# Power.net
KiCad netlist of a schematic drawn in Altium Designer
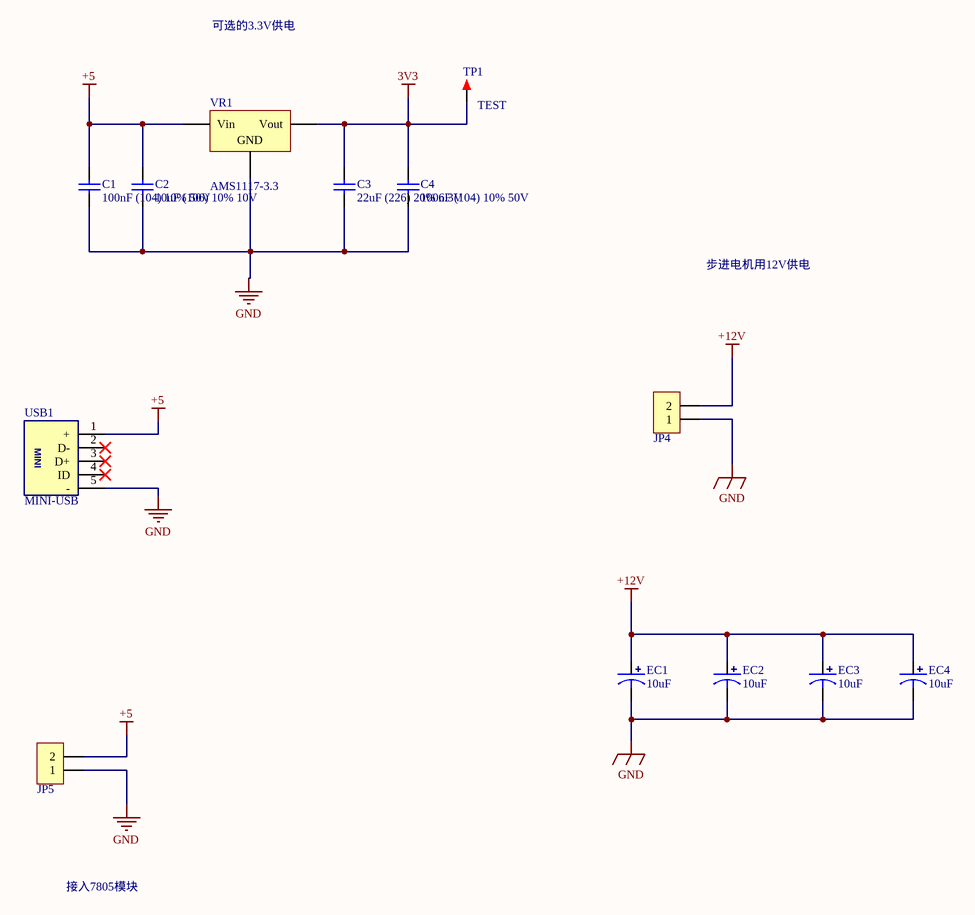
[diagram p0: Power.SchDoc]

(export (version "E")
  (design (tool "Eeschema 10.0.6"))
  (components
    (comp (ref "C1")
      (value "100nF (104) 10% 50V")
      (footprint "0603_C")
      (description "贴片电容")
      (libsource (lib "Miscellaneous Devices LC") (part "0603 100nF (104) 10% 50V"))
    )
    (comp (ref "C2")
      (value "10uF (106) 10% 10V")
      (footprint "0603_C")
      (description "贴片电容")
      (libsource (lib "Miscellaneous Devices LC") (part "0603 10uF (106) 10% 10V"))
    )
    (comp (ref "C3")
      (value "22uF (226) 20% 6.3V")
      (footprint "0603_C")
      (description "贴片电容")
      (libsource (lib "Miscellaneous Devices LC") (part "0603 22uF (226) 20% 6.3V"))
    )
    (comp (ref "C4")
      (value "100nF (104) 10% 50V")
      (footprint "0603_C")
      (description "贴片电容")
      (libsource (lib "Miscellaneous Devices LC") (part "0603 100nF (104) 10% 50V"))
    )
    (comp (ref "EC1")
      (value "10uF")
      (footprint "DIP-EC1.5X4X8")
      (description "直插电解电容")
      (libsource (lib "电容") (part "DIP_ECAP"))
    )
    (comp (ref "EC2")
      (value "10uF")
      (footprint "DIP-EC1.5X4X8")
      (description "直插电解电容")
      (libsource (lib "电容") (part "DIP_ECAP"))
    )
    (comp (ref "EC3")
      (value "10uF")
      (footprint "DIP-EC1.5X4X8")
      (description "直插电解电容")
      (libsource (lib "电容") (part "DIP_ECAP"))
    )
    (comp (ref "EC4")
      (value "10uF")
      (footprint "DIP-EC1.5X4X8")
      (description "直插电解电容")
      (libsource (lib "电容") (part "DIP_ECAP"))
    )
    (comp (ref "JP4")
      (value "HDR-1X2")
      (footprint "KF7620-2P")
      (description "2P接插件")
      (fields (field (name "版权归属") "源创客"))
      (libsource (lib "4.11 - 接插件-脚距7.62") (part "Header 2"))
    )
    (comp (ref "JP5")
      (value "HDR-1X2")
      (footprint "KF7620-2P")
      (description "2P接插件")
      (fields (field (name "版权归属") "源创客"))
      (libsource (lib "4.11 - 接插件-脚距7.62") (part "Header 2"))
    )
    (comp (ref "TP1")
      (value "TEST")
      (footprint "TEST 1")
      (description "测试点")
      (fields (field (name "版权归属") "源创客"))
      (libsource (lib "15.1 - 未分类器件") (part "TEST"))
    )
    (comp (ref "USB1") (value "MINI-USB") (footprint "USB-MINI-A") (libsource (lib "USB") (part "MINI-USB")))
    (comp (ref "VR1")
      (value "AMS1117-3.3")
      (footprint "SOT-223")
      (description "低压差线性稳压(LDO)")
      (libsource (lib "Miscellaneous Devices LC") (part "SOT-223 AMS1117-3.3"))
    )
  )
  (nets
    (net (code "1") (name "+5") (class "Default")
      (node (ref "C1") (pin "2") (pinfunction "2_2") (pintype "passive"))
      (node (ref "C2") (pin "2") (pinfunction "2_2") (pintype "passive"))
      (node (ref "JP5") (pin "2") (pinfunction "2_2") (pintype "passive"))
      (node (ref "USB1") (pin "1") (pinfunction "+_1") (pintype "passive"))
      (node (ref "VR1") (pin "3") (pinfunction "Vin_3") (pintype "passive"))
    )
    (net (code "2") (name "+12V") (class "Default")
      (node (ref "EC1") (pin "1") (pinfunction "1_1") (pintype "passive"))
      (node (ref "EC2") (pin "1") (pinfunction "1_1") (pintype "passive"))
      (node (ref "EC3") (pin "1") (pinfunction "1_1") (pintype "passive"))
      (node (ref "EC4") (pin "1") (pinfunction "1_1") (pintype "passive"))
      (node (ref "JP4") (pin "2") (pinfunction "2_2") (pintype "passive"))
    )
    (net (code "3") (name "3V3") (class "Default")
      (node (ref "C3") (pin "2") (pinfunction "2_2") (pintype "passive"))
      (node (ref "C4") (pin "2") (pinfunction "2_2") (pintype "passive"))
      (node (ref "TP1") (pin "1") (pinfunction "1_1") (pintype "passive"))
      (node (ref "VR1") (pin "2") (pinfunction "Vout_2") (pintype "passive"))
    )
    (net (code "4") (name "GND") (class "Default")
      (node (ref "C1") (pin "1") (pinfunction "1_1") (pintype "passive"))
      (node (ref "C2") (pin "1") (pinfunction "1_1") (pintype "passive"))
      (node (ref "C3") (pin "1") (pinfunction "1_1") (pintype "passive"))
      (node (ref "C4") (pin "1") (pinfunction "1_1") (pintype "passive"))
      (node (ref "EC1") (pin "2") (pinfunction "2_2") (pintype "passive"))
      (node (ref "EC2") (pin "2") (pinfunction "2_2") (pintype "passive"))
      (node (ref "EC3") (pin "2") (pinfunction "2_2") (pintype "passive"))
      (node (ref "EC4") (pin "2") (pinfunction "2_2") (pintype "passive"))
      (node (ref "JP4") (pin "1") (pinfunction "1_1") (pintype "passive"))
      (node (ref "JP5") (pin "1") (pinfunction "1_1") (pintype "passive"))
      (node (ref "USB1") (pin "5") (pinfunction "-_5") (pintype "passive"))
      (node (ref "VR1") (pin "1") (pinfunction "GND_1") (pintype "passive"))
    )
    (net (code "5") (name "unconnected-(USB1-D+-Pad3)") (class "Default")
      (node (ref "USB1") (pin "3") (pinfunction "D+_3") (pintype "passive+no_connect"))
    )
    (net (code "6") (name "unconnected-(USB1-D--Pad2)") (class "Default")
      (node (ref "USB1") (pin "2") (pinfunction "D-_2") (pintype "passive+no_connect"))
    )
    (net (code "7") (name "unconnected-(USB1-ID-Pad4)") (class "Default")
      (node (ref "USB1") (pin "4") (pinfunction "ID_4") (pintype "passive+no_connect"))
    )
  )
)
